# SCH_qrist0pf_Proj3_LED_2023-04-06.net
KiCad netlist of a schematic drawn in EasyEDA
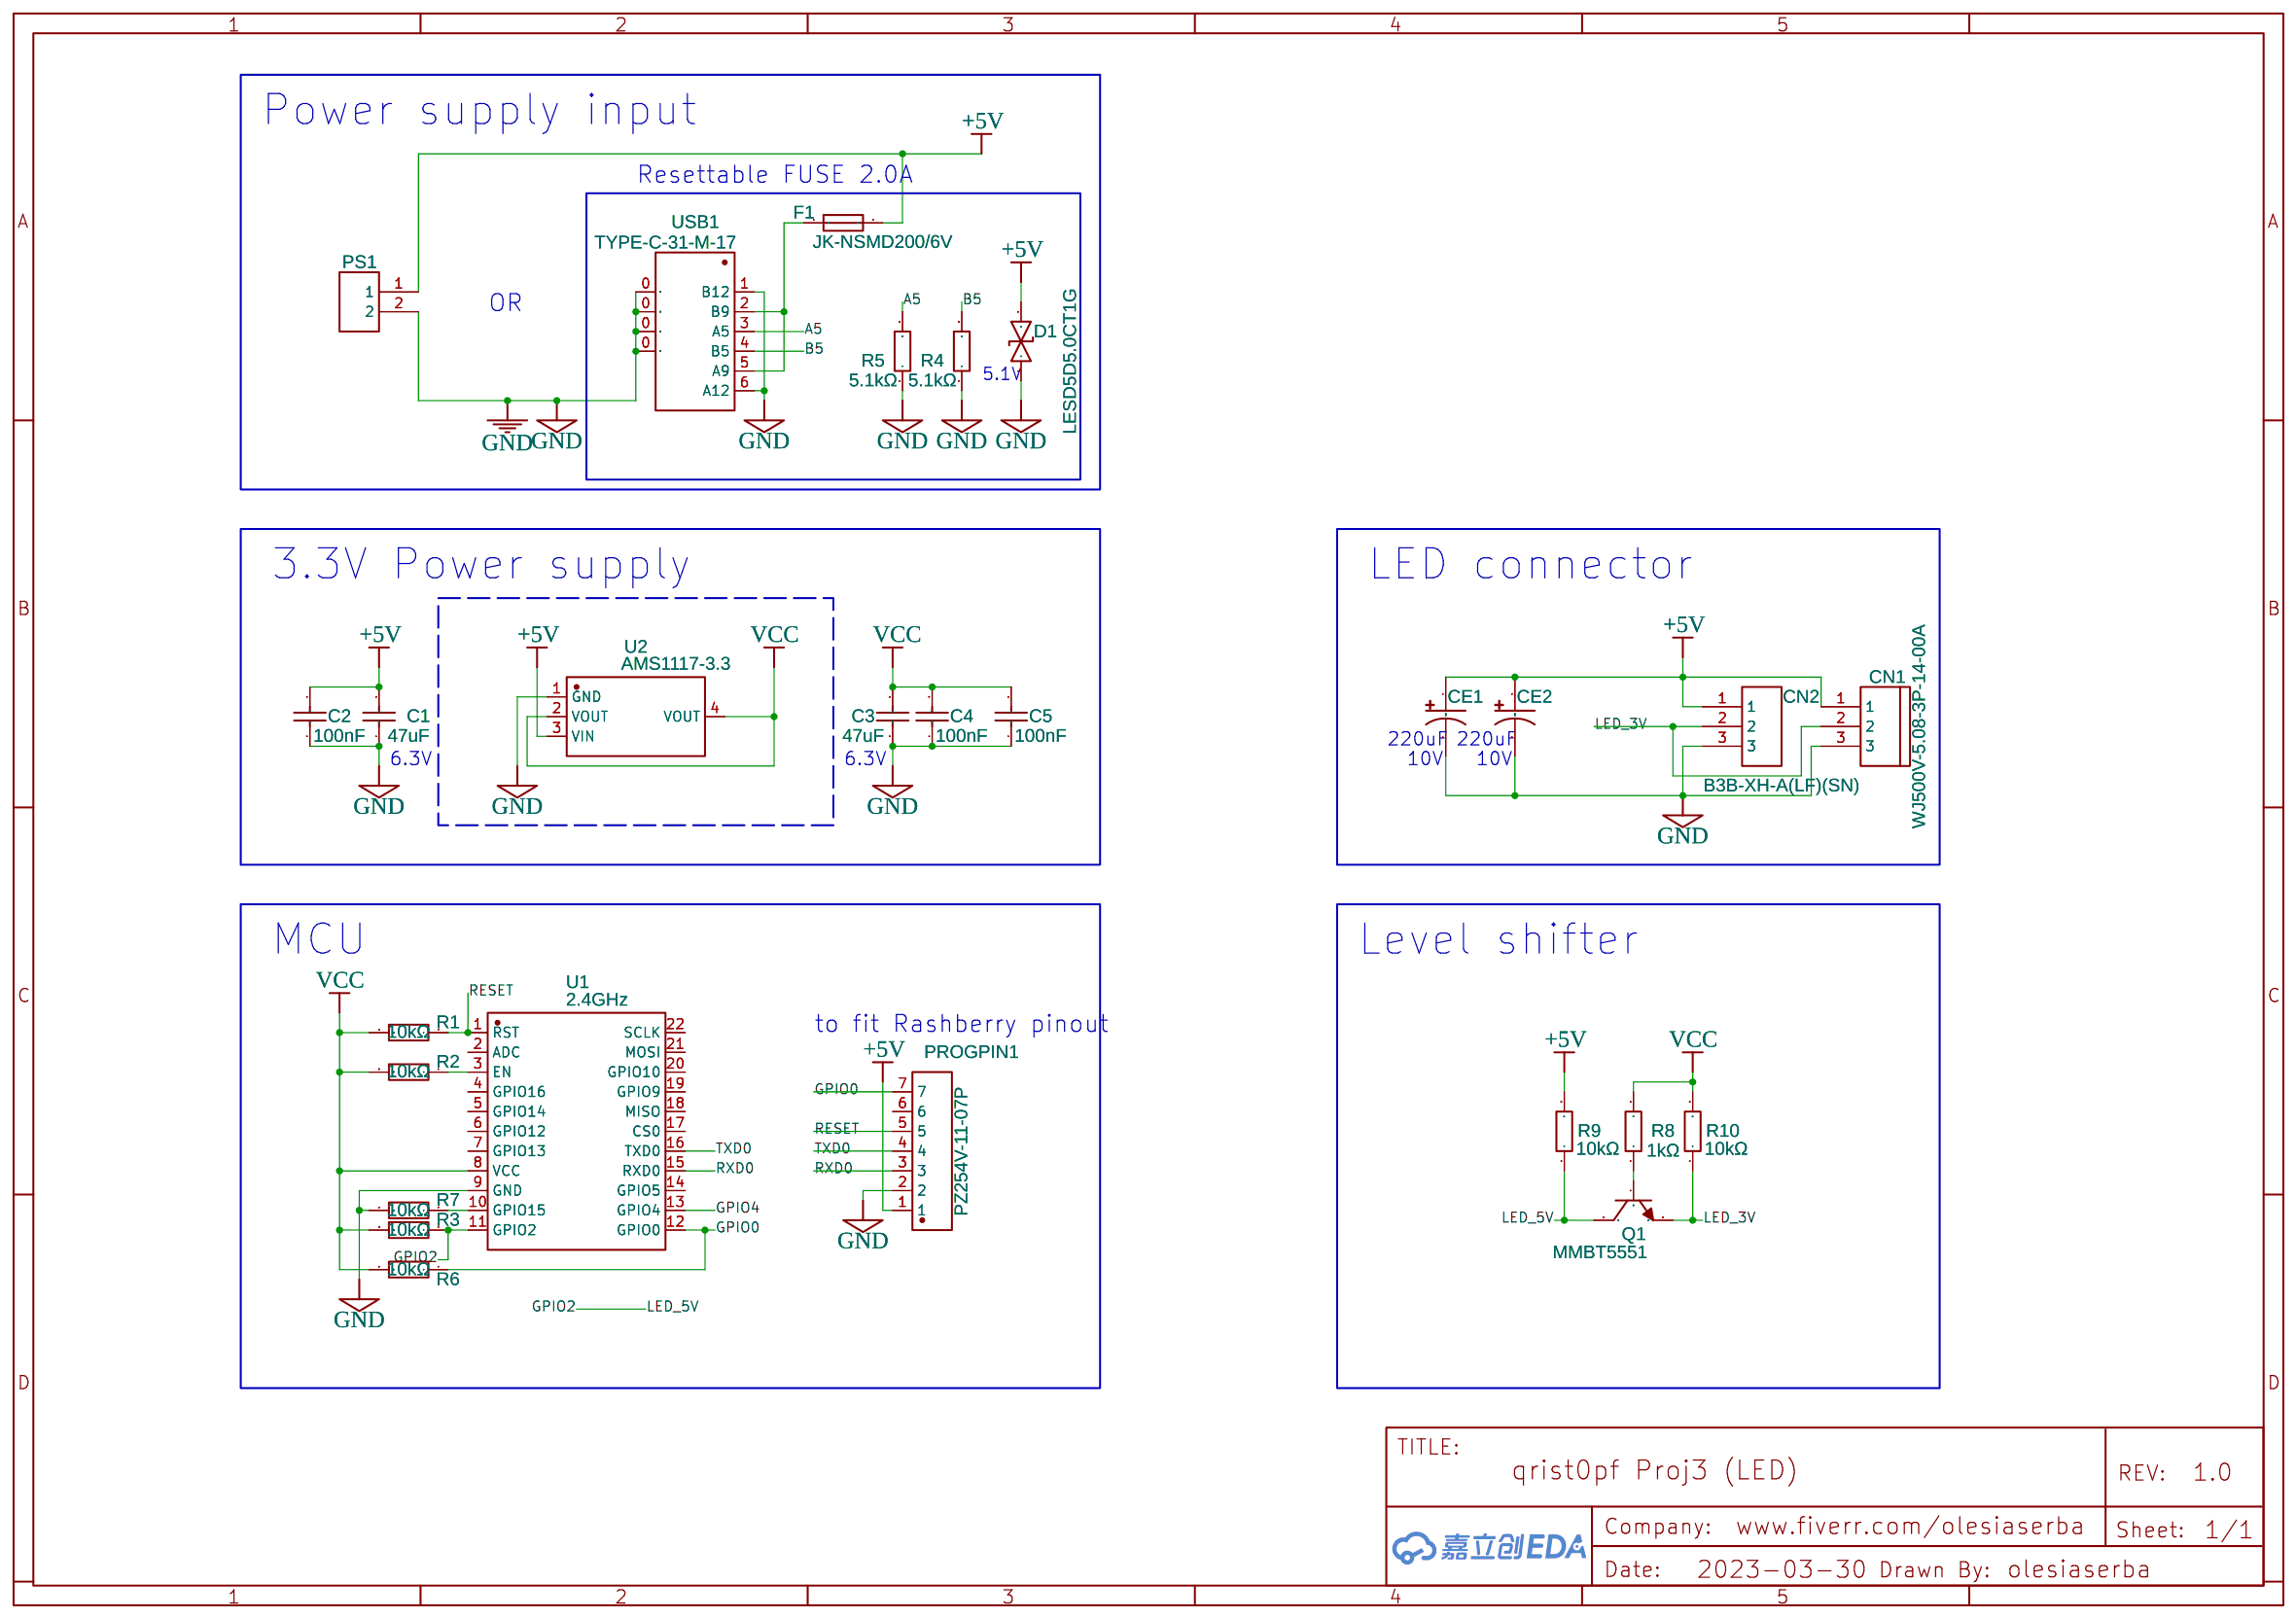
[diagram p0: schematic sheet]

(export (version "E")
  (design (tool "Eeschema 10.0.6"))
  (components
    (comp (ref "C1")
      (value "47uF")
      (fields
        (field (name "BOM_Manufacturer Part") "CL21A476MQYNNNE")
        (field (name "BOM_Supplier Part") "C16780")
      )
      (libsource (lib "") (part "CL21A476MQYNNNE"))
    )
    (comp (ref "C2")
      (value "100nF")
      (fields
        (field (name "BOM_Manufacturer Part") "CC0805KRX7R9BB104")
        (field (name "BOM_Supplier Part") "C49678")
      )
      (libsource (lib "") (part "CC0805KRX7R9BB104"))
    )
    (comp (ref "C3")
      (value "47uF")
      (fields
        (field (name "BOM_Manufacturer Part") "CL21A476MQYNNNE")
        (field (name "BOM_Supplier Part") "C16780")
      )
      (libsource (lib "") (part "CL21A476MQYNNNE_1"))
    )
    (comp (ref "C4")
      (value "100nF")
      (fields
        (field (name "BOM_Manufacturer Part") "CC0805KRX7R9BB104")
        (field (name "BOM_Supplier Part") "C49678")
      )
      (libsource (lib "") (part "CC0805KRX7R9BB104"))
    )
    (comp (ref "C5")
      (value "100nF")
      (fields
        (field (name "BOM_Manufacturer Part") "CC0805KRX7R9BB104")
        (field (name "BOM_Supplier Part") "C49678")
      )
      (libsource (lib "") (part "CC0805KRX7R9BB104"))
    )
    (comp (ref "CE1")
      (value "220uF")
      (fields
        (field (name "BOM_Manufacturer Part") "RVT1A221M0607")
        (field (name "BOM_Supplier Part") "C87859")
      )
      (libsource (lib "") (part "RVT1A221M0607_C87859"))
    )
    (comp (ref "CE2")
      (value "220uF")
      (fields
        (field (name "BOM_Manufacturer Part") "RVT1A221M0607")
        (field (name "BOM_Supplier Part") "C87859")
      )
      (libsource (lib "") (part "RVT1A221M0607_C87859"))
    )
    (comp (ref "CN1")
      (value "WJ500V-5.08-3P-14-00A")
      (fields
        (field (name "BOM_Manufacturer Part") "WJ500V-5.08-3P")
        (field (name "BOM_Supplier Part") "C72334")
      )
      (libsource (lib "") (part "WJ500V-5.08-3P-14-00A"))
    )
    (comp (ref "CN2")
      (value "B3B-XH-A(LF)(SN)")
      (fields (field (name "BOM_Supplier Part") "C144394"))
      (libsource (lib "") (part "B3B-XH-A(LF)(SN)"))
    )
    (comp (ref "D1")
      (value "LESD5D5.0CT1G")
      (fields (field (name "BOM_Supplier Part") "C383211"))
      (libsource (lib "") (part "LESD5D5.0CT1G"))
    )
    (comp (ref "F1")
      (value "JK-NSMD200/6V")
      (fields
        (field (name "BOM_Manufacturer Part") "JK-nSMD200/6V")
        (field (name "BOM_Supplier Part") "C2830251")
      )
      (libsource (lib "") (part "JK-NSMD200/6V"))
    )
    (comp (ref "PROGPIN1")
      (value "PZ254V-11-07P")
      (fields (field (name "BOM_Supplier Part") "C492406"))
      (libsource (lib "") (part "PZ254V-11-07P"))
    )
    (comp (ref "PS1")
      (value "WJ500V-5.08-2P-14-00A")
      (fields (field (name "BOM_Supplier Part") "C8465"))
      (libsource (lib "") (part "WJ500V-5.08-2P-14-00A"))
    )
    (comp (ref "Q1")
      (value "MMBT5551")
      (fields (field (name "BOM_Supplier Part") "C2145"))
      (libsource (lib "") (part "MMBT5551_C2145"))
    )
    (comp (ref "R1")
      (value "10kΩ")
      (fields
        (field (name "BOM_Manufacturer Part") "0402WGF1002TCE")
        (field (name "BOM_Supplier Part") "C25744")
      )
      (libsource (lib "") (part "0402WGF1002TCE_1"))
    )
    (comp (ref "R2")
      (value "10kΩ")
      (fields
        (field (name "BOM_Manufacturer Part") "0402WGF1002TCE")
        (field (name "BOM_Supplier Part") "C25744")
      )
      (libsource (lib "") (part "0402WGF1002TCE_1"))
    )
    (comp (ref "R3")
      (value "10kΩ")
      (fields
        (field (name "BOM_Manufacturer Part") "0402WGF1002TCE")
        (field (name "BOM_Supplier Part") "C25744")
      )
      (libsource (lib "") (part "0402WGF1002TCE_1"))
    )
    (comp (ref "R4")
      (value "5.1kΩ")
      (fields
        (field (name "BOM_Manufacturer Part") "0603WAF5101T5E")
        (field (name "BOM_Supplier Part") "C23186")
      )
      (libsource (lib "") (part "0603WAF5101T5E"))
    )
    (comp (ref "R5")
      (value "5.1kΩ")
      (fields
        (field (name "BOM_Manufacturer Part") "0603WAF5101T5E")
        (field (name "BOM_Supplier Part") "C23186")
      )
      (libsource (lib "") (part "0603WAF5101T5E"))
    )
    (comp (ref "R6")
      (value "10kΩ")
      (fields
        (field (name "BOM_Manufacturer Part") "0402WGF1002TCE")
        (field (name "BOM_Supplier Part") "C25744")
      )
      (libsource (lib "") (part "0402WGF1002TCE_1"))
    )
    (comp (ref "R7")
      (value "10kΩ")
      (fields
        (field (name "BOM_Manufacturer Part") "0402WGF1002TCE")
        (field (name "BOM_Supplier Part") "C25744")
      )
      (libsource (lib "") (part "0402WGF1002TCE_1"))
    )
    (comp (ref "R8")
      (value "1kΩ")
      (fields
        (field (name "BOM_Manufacturer Part") "0402WGF1001TCE")
        (field (name "BOM_Supplier Part") "C11702")
      )
      (libsource (lib "") (part "0402WGF1001TCE"))
    )
    (comp (ref "R9")
      (value "10kΩ")
      (fields
        (field (name "BOM_Manufacturer Part") "0402WGF1002TCE")
        (field (name "BOM_Supplier Part") "C25744")
      )
      (libsource (lib "") (part "0402WGF1002TCE"))
    )
    (comp (ref "R10")
      (value "10kΩ")
      (fields
        (field (name "BOM_Manufacturer Part") "0402WGF1002TCE")
        (field (name "BOM_Supplier Part") "C25744")
      )
      (libsource (lib "") (part "0402WGF1002TCE"))
    )
    (comp (ref "U1")
      (value "2.4GHz")
      (fields
        (field (name "BOM_Manufacturer Part") "ESP-12F(ESP8266MOD)")
        (field (name "BOM_Supplier Part") "C82891")
      )
      (libsource (lib "") (part "ESP-12F(ESP8266MOD)"))
    )
    (comp (ref "U2")
      (value "AMS1117-3.3")
      (fields (field (name "BOM_Supplier Part") "C6186"))
      (libsource (lib "") (part "AMS1117-3.3"))
    )
    (comp (ref "USB1")
      (value "TYPE-C-31-M-17")
      (fields (field (name "BOM_Supplier Part") "C283540"))
      (libsource (lib "") (part "TYPE-C-31-M-17"))
    )
  )
  (nets
    (net (code "1") (name "+5V") (class "Default")
      (node (ref "C1") (pin "2") (pinfunction "2_2") (pintype "input"))
      (node (ref "C2") (pin "2") (pinfunction "2_2") (pintype "input"))
      (node (ref "CE1") (pin "1") (pinfunction "1_1") (pintype "unspecified"))
      (node (ref "CE2") (pin "1") (pinfunction "1_1") (pintype "unspecified"))
      (node (ref "CN1") (pin "1") (pinfunction "1_1") (pintype "unspecified"))
      (node (ref "CN2") (pin "1") (pinfunction "1_1") (pintype "unspecified"))
      (node (ref "D1") (pin "2") (pinfunction "2_2") (pintype "unspecified"))
      (node (ref "F1") (pin "2") (pinfunction "2_2") (pintype "unspecified"))
      (node (ref "PROGPIN1") (pin "1") (pinfunction "1_1") (pintype "unspecified"))
      (node (ref "PS1") (pin "1") (pinfunction "1_1") (pintype "unspecified"))
      (node (ref "R9") (pin "2") (pinfunction "2_2") (pintype "input"))
      (node (ref "U2") (pin "3") (pinfunction "VIN_3") (pintype "unspecified"))
    )
    (net (code "2") (name "/A5") (class "Default")
      (node (ref "R5") (pin "2") (pinfunction "2_2") (pintype "input"))
      (node (ref "USB1") (pin "3") (pinfunction "A5_3") (pintype "unspecified"))
    )
    (net (code "3") (name "/B5") (class "Default")
      (node (ref "R4") (pin "2") (pinfunction "2_2") (pintype "input"))
      (node (ref "USB1") (pin "4") (pinfunction "B5_4") (pintype "unspecified"))
    )
    (net (code "4") (name "/GPIO0") (class "Default")
      (node (ref "PROGPIN1") (pin "7") (pinfunction "7_7") (pintype "unspecified"))
      (node (ref "R6") (pin "1") (pinfunction "1_1") (pintype "input"))
      (node (ref "U1") (pin "12") (pinfunction "GPIO0_12") (pintype "unspecified"))
    )
    (net (code "5") (name "/GPIO2") (class "Default")
      (node (ref "Q1") (pin "3") (pinfunction "C_3") (pintype "unspecified"))
      (node (ref "R3") (pin "1") (pinfunction "1_1") (pintype "input"))
      (node (ref "R9") (pin "1") (pinfunction "1_1") (pintype "input"))
      (node (ref "U1") (pin "11") (pinfunction "GPIO2_11") (pintype "unspecified"))
    )
    (net (code "6") (name "/GPIO4") (class "Default")
      (node (ref "U1") (pin "13") (pinfunction "GPIO4_13") (pintype "unspecified"))
    )
    (net (code "7") (name "/LED_3V") (class "Default")
      (node (ref "CN1") (pin "2") (pinfunction "2_2") (pintype "unspecified"))
      (node (ref "CN2") (pin "2") (pinfunction "2_2") (pintype "unspecified"))
      (node (ref "Q1") (pin "2") (pinfunction "E_2") (pintype "unspecified"))
      (node (ref "R10") (pin "1") (pinfunction "1_1") (pintype "input"))
    )
    (net (code "8") (name "/RESET") (class "Default")
      (node (ref "PROGPIN1") (pin "5") (pinfunction "5_5") (pintype "unspecified"))
      (node (ref "R1") (pin "1") (pinfunction "1_1") (pintype "input"))
      (node (ref "U1") (pin "1") (pinfunction "RST_1") (pintype "unspecified"))
    )
    (net (code "9") (name "/RXD0") (class "Default")
      (node (ref "PROGPIN1") (pin "3") (pinfunction "3_3") (pintype "unspecified"))
      (node (ref "U1") (pin "15") (pinfunction "RXD0_15") (pintype "unspecified"))
    )
    (net (code "10") (name "/TXD0") (class "Default")
      (node (ref "PROGPIN1") (pin "4") (pinfunction "4_4") (pintype "unspecified"))
      (node (ref "U1") (pin "16") (pinfunction "TXD0_16") (pintype "unspecified"))
    )
    (net (code "11") (name "GND") (class "Default")
      (node (ref "C1") (pin "1") (pinfunction "1_1") (pintype "input"))
      (node (ref "C2") (pin "1") (pinfunction "1_1") (pintype "input"))
      (node (ref "C3") (pin "1") (pinfunction "1_1") (pintype "input"))
      (node (ref "C4") (pin "1") (pinfunction "1_1") (pintype "input"))
      (node (ref "C5") (pin "1") (pinfunction "1_1") (pintype "input"))
      (node (ref "CE1") (pin "2") (pinfunction "2_2") (pintype "unspecified"))
      (node (ref "CE2") (pin "2") (pinfunction "2_2") (pintype "unspecified"))
      (node (ref "CN1") (pin "3") (pinfunction "3_3") (pintype "unspecified"))
      (node (ref "CN2") (pin "3") (pinfunction "3_3") (pintype "unspecified"))
      (node (ref "D1") (pin "1") (pinfunction "1_1") (pintype "unspecified"))
      (node (ref "PROGPIN1") (pin "2") (pinfunction "2_2") (pintype "unspecified"))
      (node (ref "PS1") (pin "2") (pinfunction "2_2") (pintype "unspecified"))
      (node (ref "R4") (pin "1") (pinfunction "1_1") (pintype "input"))
      (node (ref "R5") (pin "1") (pinfunction "1_1") (pintype "input"))
      (node (ref "R7") (pin "2") (pinfunction "2_2") (pintype "input"))
      (node (ref "U1") (pin "9") (pinfunction "GND_9") (pintype "unspecified"))
      (node (ref "U2") (pin "1") (pinfunction "GND_1") (pintype "unspecified"))
      (node (ref "USB1") (pin "0") (pinfunction "0_0") (pintype "unspecified"))
      (node (ref "USB1") (pin "1") (pinfunction "B12_1") (pintype "unspecified"))
      (node (ref "USB1") (pin "6") (pinfunction "A12_6") (pintype "unspecified"))
    )
    (net (code "12") (name "Net-(Q1-B)") (class "Default")
      (node (ref "Q1") (pin "1") (pinfunction "B_1") (pintype "unspecified"))
      (node (ref "R8") (pin "1") (pinfunction "1_1") (pintype "input"))
    )
    (net (code "13") (name "Net-(U1-EN)") (class "Default")
      (node (ref "R2") (pin "1") (pinfunction "1_1") (pintype "input"))
      (node (ref "U1") (pin "3") (pinfunction "EN_3") (pintype "unspecified"))
    )
    (net (code "14") (name "Net-(U1-GPIO15)") (class "Default")
      (node (ref "R7") (pin "1") (pinfunction "1_1") (pintype "input"))
      (node (ref "U1") (pin "10") (pinfunction "GPIO15_10") (pintype "unspecified"))
    )
    (net (code "15") (name "Net-(USB1-A9)") (class "Default")
      (node (ref "F1") (pin "1") (pinfunction "1_1") (pintype "unspecified"))
      (node (ref "USB1") (pin "2") (pinfunction "B9_2") (pintype "unspecified"))
      (node (ref "USB1") (pin "5") (pinfunction "A9_5") (pintype "unspecified"))
    )
    (net (code "16") (name "VCC") (class "Default")
      (node (ref "C3") (pin "2") (pinfunction "2_2") (pintype "input"))
      (node (ref "C4") (pin "2") (pinfunction "2_2") (pintype "input"))
      (node (ref "C5") (pin "2") (pinfunction "2_2") (pintype "input"))
      (node (ref "R1") (pin "2") (pinfunction "2_2") (pintype "input"))
      (node (ref "R10") (pin "2") (pinfunction "2_2") (pintype "input"))
      (node (ref "R2") (pin "2") (pinfunction "2_2") (pintype "input"))
      (node (ref "R3") (pin "2") (pinfunction "2_2") (pintype "input"))
      (node (ref "R6") (pin "2") (pinfunction "2_2") (pintype "input"))
      (node (ref "R8") (pin "2") (pinfunction "2_2") (pintype "input"))
      (node (ref "U1") (pin "8") (pinfunction "VCC_8") (pintype "unspecified"))
      (node (ref "U2") (pin "2") (pinfunction "VOUT_2") (pintype "unspecified"))
      (node (ref "U2") (pin "4") (pinfunction "VOUT_4") (pintype "unspecified"))
    )
    (net (code "17") (name "unconnected-(PROGPIN1-Pad6)") (class "Default")
      (node (ref "PROGPIN1") (pin "6") (pinfunction "6_6") (pintype "unspecified"))
    )
    (net (code "18") (name "unconnected-(U1-ADC-Pad2)") (class "Default")
      (node (ref "U1") (pin "2") (pinfunction "ADC_2") (pintype "unspecified"))
    )
    (net (code "19") (name "unconnected-(U1-CS0-Pad17)") (class "Default")
      (node (ref "U1") (pin "17") (pinfunction "CS0_17") (pintype "unspecified"))
    )
    (net (code "20") (name "unconnected-(U1-GPIO5-Pad14)") (class "Default")
      (node (ref "U1") (pin "14") (pinfunction "GPIO5_14") (pintype "unspecified"))
    )
    (net (code "21") (name "unconnected-(U1-GPIO9-Pad19)") (class "Default")
      (node (ref "U1") (pin "19") (pinfunction "GPIO9_19") (pintype "unspecified"))
    )
    (net (code "22") (name "unconnected-(U1-GPIO10-Pad20)") (class "Default")
      (node (ref "U1") (pin "20") (pinfunction "GPIO10_20") (pintype "unspecified"))
    )
    (net (code "23") (name "unconnected-(U1-GPIO12-Pad6)") (class "Default")
      (node (ref "U1") (pin "6") (pinfunction "GPIO12_6") (pintype "unspecified"))
    )
    (net (code "24") (name "unconnected-(U1-GPIO13-Pad7)") (class "Default")
      (node (ref "U1") (pin "7") (pinfunction "GPIO13_7") (pintype "unspecified"))
    )
    (net (code "25") (name "unconnected-(U1-GPIO14-Pad5)") (class "Default")
      (node (ref "U1") (pin "5") (pinfunction "GPIO14_5") (pintype "unspecified"))
    )
    (net (code "26") (name "unconnected-(U1-GPIO16-Pad4)") (class "Default")
      (node (ref "U1") (pin "4") (pinfunction "GPIO16_4") (pintype "unspecified"))
    )
    (net (code "27") (name "unconnected-(U1-MISO-Pad18)") (class "Default")
      (node (ref "U1") (pin "18") (pinfunction "MISO_18") (pintype "unspecified"))
    )
    (net (code "28") (name "unconnected-(U1-MOSI-Pad21)") (class "Default")
      (node (ref "U1") (pin "21") (pinfunction "MOSI_21") (pintype "unspecified"))
    )
    (net (code "29") (name "unconnected-(U1-SCLK-Pad22)") (class "Default")
      (node (ref "U1") (pin "22") (pinfunction "SCLK_22") (pintype "unspecified"))
    )
  )
)
